# ReceiverShield.net
KiCad netlist of a schematic drawn in EAGLE
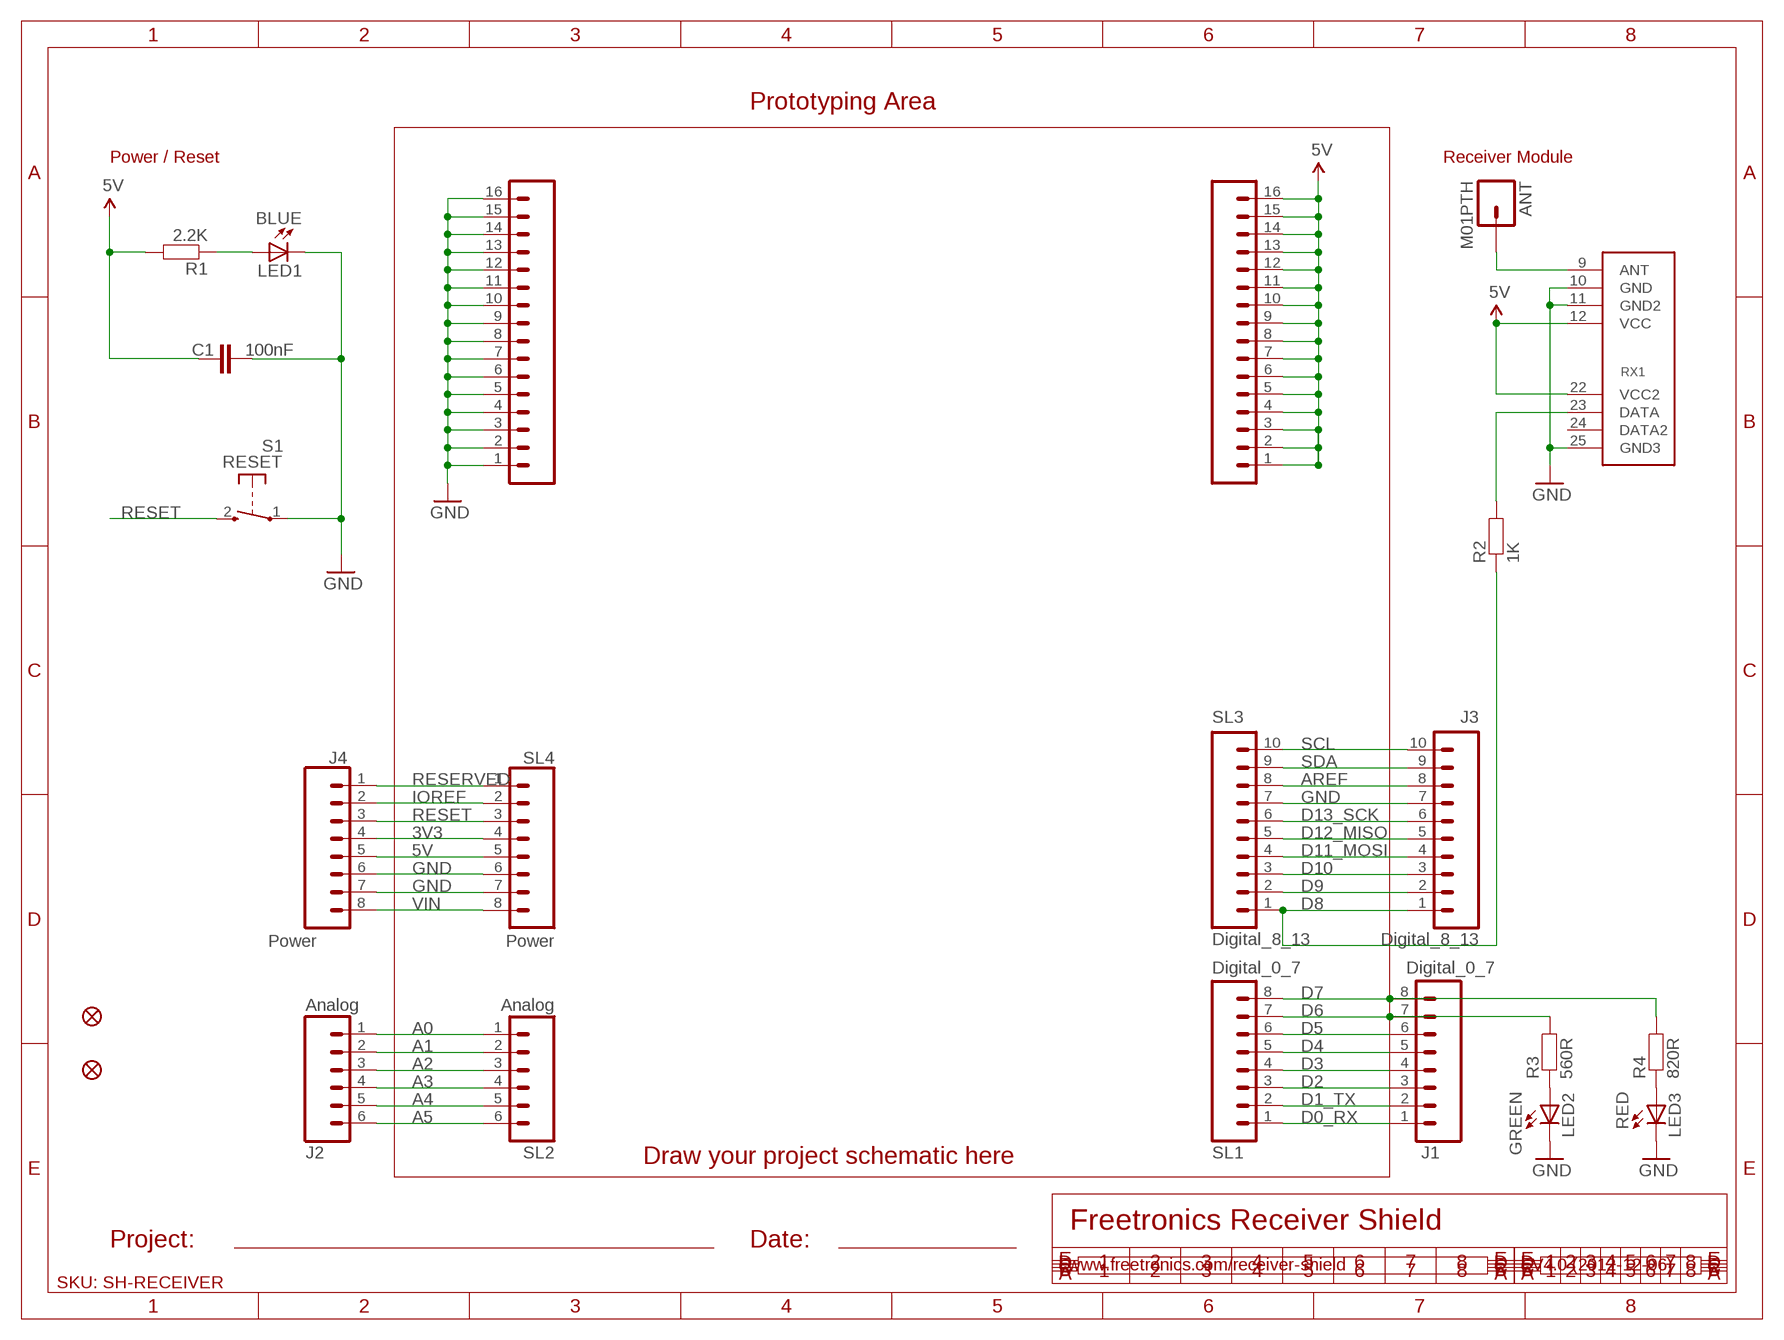
[diagram p0: schematic, sheet 1]

(export (version "E")
  (design (tool "Eeschema 10.0.6"))
  (components
    (comp (ref "ANT")
      (value "M01PTH")
      (footprint "eagle-import:1X01")
      (libsource (lib "eagle-import") (part "M01PTH"))
    )
    (comp (ref "C1")
      (value "100nF")
      (footprint "eagle-import:0603")
      (libsource (lib "eagle-import") (part "CAP0603"))
    )
    (comp (ref "J1")
      (value "Digital_0_7")
      (footprint "eagle-import:1X08")
      (libsource (lib "eagle-import") (part "M08"))
    )
    (comp (ref "J2")
      (value "Analog")
      (footprint "eagle-import:1X06")
      (libsource (lib "eagle-import") (part "M06SIP"))
    )
    (comp (ref "J3")
      (value "Digital_8_13")
      (footprint "eagle-import:1X10")
      (libsource (lib "eagle-import") (part "M100.1"))
    )
    (comp (ref "J4")
      (value "Power")
      (footprint "eagle-import:1X08")
      (libsource (lib "eagle-import") (part "M08"))
    )
    (comp (ref "LED1")
      (value "BLUE")
      (footprint "eagle-import:LED-0603")
      (libsource (lib "eagle-import") (part "LED0603"))
    )
    (comp (ref "LED2")
      (value "GREEN")
      (footprint "eagle-import:LED-0603")
      (libsource (lib "eagle-import") (part "LED0603"))
    )
    (comp (ref "LED3")
      (value "RED")
      (footprint "eagle-import:LED-0603")
      (libsource (lib "eagle-import") (part "LED0603"))
    )
    (comp (ref "PADS_5V")
      (value "M16PTH")
      (footprint "eagle-import:1X16")
      (libsource (lib "eagle-import") (part "M16PTH"))
    )
    (comp (ref "PADS_GND")
      (value "M16PTH")
      (footprint "eagle-import:1X16")
      (libsource (lib "eagle-import") (part "M16PTH"))
    )
    (comp (ref "R1")
      (value "2.2K")
      (footprint "eagle-import:0603")
      (libsource (lib "eagle-import") (part "RESISTOR0603"))
    )
    (comp (ref "R2")
      (value "1K")
      (footprint "eagle-import:0603")
      (libsource (lib "eagle-import") (part "RESISTOR0603"))
    )
    (comp (ref "R3")
      (value "560R")
      (footprint "eagle-import:0603")
      (libsource (lib "eagle-import") (part "RESISTOR0603"))
    )
    (comp (ref "R4")
      (value "820R")
      (footprint "eagle-import:0603")
      (libsource (lib "eagle-import") (part "RESISTOR0603"))
    )
    (comp (ref "RX1")
      (value "RXB1SIL")
      (footprint "eagle-import:RX-B1")
      (libsource (lib "eagle-import") (part "RXB1SIL"))
    )
    (comp (ref "S1")
      (value "RESET")
      (footprint "eagle-import:TACTILE_SWITCH_SMD_2PIN_TINY")
      (libsource (lib "eagle-import") (part "TAC_SWITCH_2PIN"))
    )
    (comp (ref "SL1")
      (value "Digital_0_7")
      (footprint "eagle-import:1X08")
      (libsource (lib "eagle-import") (part "M08"))
    )
    (comp (ref "SL2")
      (value "Analog")
      (footprint "eagle-import:1X06")
      (libsource (lib "eagle-import") (part "M06SIP"))
    )
    (comp (ref "SL3")
      (value "Digital_8_13")
      (footprint "eagle-import:1X10")
      (libsource (lib "eagle-import") (part "M100.1"))
    )
    (comp (ref "SL4")
      (value "Power")
      (footprint "eagle-import:1X08")
      (libsource (lib "eagle-import") (part "M08"))
    )
    (comp (ref "U$4")
      (value "FIDUCIAL1X2.5")
      (footprint "eagle-import:FIDUCIAL-1X2.5")
      (libsource (lib "eagle-import") (part "FIDUCIAL1X2.5"))
    )
    (comp (ref "U$5")
      (value "FIDUCIAL1X2.5")
      (footprint "eagle-import:FIDUCIAL-1X2.5")
      (libsource (lib "eagle-import") (part "FIDUCIAL1X2.5"))
    )
  )
  (nets
    (net (code "1") (name "/3V3") (class "Default")
      (node (ref "J4") (pin "4") (pinfunction "4_4") (pintype "passive"))
      (node (ref "SL4") (pin "4") (pinfunction "4_4") (pintype "passive"))
    )
    (net (code "2") (name "/A0") (class "Default")
      (node (ref "J2") (pin "1") (pinfunction "1_1") (pintype "passive"))
      (node (ref "SL2") (pin "1") (pinfunction "1_1") (pintype "passive"))
    )
    (net (code "3") (name "/A1") (class "Default")
      (node (ref "J2") (pin "2") (pinfunction "2_2") (pintype "passive"))
      (node (ref "SL2") (pin "2") (pinfunction "2_2") (pintype "passive"))
    )
    (net (code "4") (name "/A2") (class "Default")
      (node (ref "J2") (pin "3") (pinfunction "3_3") (pintype "passive"))
      (node (ref "SL2") (pin "3") (pinfunction "3_3") (pintype "passive"))
    )
    (net (code "5") (name "/A3") (class "Default")
      (node (ref "J2") (pin "4") (pinfunction "4_4") (pintype "passive"))
      (node (ref "SL2") (pin "4") (pinfunction "4_4") (pintype "passive"))
    )
    (net (code "6") (name "/A4") (class "Default")
      (node (ref "J2") (pin "5") (pinfunction "5_5") (pintype "passive"))
      (node (ref "SL2") (pin "5") (pinfunction "5_5") (pintype "passive"))
    )
    (net (code "7") (name "/A5") (class "Default")
      (node (ref "J2") (pin "6") (pinfunction "6_6") (pintype "passive"))
      (node (ref "SL2") (pin "6") (pinfunction "6_6") (pintype "passive"))
    )
    (net (code "8") (name "/AREF") (class "Default")
      (node (ref "J3") (pin "8") (pinfunction "8_8") (pintype "passive"))
      (node (ref "SL3") (pin "8") (pinfunction "8_8") (pintype "passive"))
    )
    (net (code "9") (name "/D0_RX") (class "Default")
      (node (ref "J1") (pin "1") (pinfunction "1_1") (pintype "passive"))
      (node (ref "SL1") (pin "1") (pinfunction "1_1") (pintype "passive"))
    )
    (net (code "10") (name "/D1_TX") (class "Default")
      (node (ref "J1") (pin "2") (pinfunction "2_2") (pintype "passive"))
      (node (ref "SL1") (pin "2") (pinfunction "2_2") (pintype "passive"))
    )
    (net (code "11") (name "/D2") (class "Default")
      (node (ref "J1") (pin "3") (pinfunction "3_3") (pintype "passive"))
      (node (ref "SL1") (pin "3") (pinfunction "3_3") (pintype "passive"))
    )
    (net (code "12") (name "/D3") (class "Default")
      (node (ref "J1") (pin "4") (pinfunction "4_4") (pintype "passive"))
      (node (ref "SL1") (pin "4") (pinfunction "4_4") (pintype "passive"))
    )
    (net (code "13") (name "/D4") (class "Default")
      (node (ref "J1") (pin "5") (pinfunction "5_5") (pintype "passive"))
      (node (ref "SL1") (pin "5") (pinfunction "5_5") (pintype "passive"))
    )
    (net (code "14") (name "/D5") (class "Default")
      (node (ref "J1") (pin "6") (pinfunction "6_6") (pintype "passive"))
      (node (ref "SL1") (pin "6") (pinfunction "6_6") (pintype "passive"))
    )
    (net (code "15") (name "/D6") (class "Default")
      (node (ref "J1") (pin "7") (pinfunction "7_7") (pintype "passive"))
      (node (ref "R3") (pin "2") (pinfunction "2_2") (pintype "passive"))
      (node (ref "SL1") (pin "7") (pinfunction "7_7") (pintype "passive"))
    )
    (net (code "16") (name "/D7") (class "Default")
      (node (ref "J1") (pin "8") (pinfunction "8_8") (pintype "passive"))
      (node (ref "R4") (pin "2") (pinfunction "2_2") (pintype "passive"))
      (node (ref "SL1") (pin "8") (pinfunction "8_8") (pintype "passive"))
    )
    (net (code "17") (name "/D8") (class "Default")
      (node (ref "J3") (pin "1") (pinfunction "1_1") (pintype "passive"))
      (node (ref "R2") (pin "1") (pinfunction "1_1") (pintype "passive"))
      (node (ref "SL3") (pin "1") (pinfunction "1_1") (pintype "passive"))
    )
    (net (code "18") (name "/D9") (class "Default")
      (node (ref "J3") (pin "2") (pinfunction "2_2") (pintype "passive"))
      (node (ref "SL3") (pin "2") (pinfunction "2_2") (pintype "passive"))
    )
    (net (code "19") (name "/D10") (class "Default")
      (node (ref "J3") (pin "3") (pinfunction "3_3") (pintype "passive"))
      (node (ref "SL3") (pin "3") (pinfunction "3_3") (pintype "passive"))
    )
    (net (code "20") (name "/D11_MOSI") (class "Default")
      (node (ref "J3") (pin "4") (pinfunction "4_4") (pintype "passive"))
      (node (ref "SL3") (pin "4") (pinfunction "4_4") (pintype "passive"))
    )
    (net (code "21") (name "/D12_MISO") (class "Default")
      (node (ref "J3") (pin "5") (pinfunction "5_5") (pintype "passive"))
      (node (ref "SL3") (pin "5") (pinfunction "5_5") (pintype "passive"))
    )
    (net (code "22") (name "/D13_SCK") (class "Default")
      (node (ref "J3") (pin "6") (pinfunction "6_6") (pintype "passive"))
      (node (ref "SL3") (pin "6") (pinfunction "6_6") (pintype "passive"))
    )
    (net (code "23") (name "/IOREF") (class "Default")
      (node (ref "J4") (pin "2") (pinfunction "2_2") (pintype "passive"))
      (node (ref "SL4") (pin "2") (pinfunction "2_2") (pintype "passive"))
    )
    (net (code "24") (name "/RESERVED") (class "Default")
      (node (ref "J4") (pin "1") (pinfunction "1_1") (pintype "passive"))
      (node (ref "SL4") (pin "1") (pinfunction "1_1") (pintype "passive"))
    )
    (net (code "25") (name "/RESET") (class "Default")
      (node (ref "J4") (pin "3") (pinfunction "3_3") (pintype "passive"))
      (node (ref "S1") (pin "2") (pinfunction "S_2") (pintype "passive"))
      (node (ref "SL4") (pin "3") (pinfunction "3_3") (pintype "passive"))
    )
    (net (code "26") (name "/SCL") (class "Default")
      (node (ref "J3") (pin "10") (pinfunction "10_10") (pintype "passive"))
      (node (ref "SL3") (pin "10") (pinfunction "10_10") (pintype "passive"))
    )
    (net (code "27") (name "/SDA") (class "Default")
      (node (ref "J3") (pin "9") (pinfunction "9_9") (pintype "passive"))
      (node (ref "SL3") (pin "9") (pinfunction "9_9") (pintype "passive"))
    )
    (net (code "28") (name "/VIN") (class "Default")
      (node (ref "J4") (pin "8") (pinfunction "8_8") (pintype "passive"))
      (node (ref "SL4") (pin "8") (pinfunction "8_8") (pintype "passive"))
    )
    (net (code "29") (name "5V") (class "Default")
      (node (ref "C1") (pin "1") (pinfunction "1_1") (pintype "passive"))
      (node (ref "J4") (pin "5") (pinfunction "5_5") (pintype "passive"))
      (node (ref "PADS_5V") (pin "1") (pinfunction "1_1") (pintype "passive"))
      (node (ref "PADS_5V") (pin "10") (pinfunction "10_10") (pintype "passive"))
      (node (ref "PADS_5V") (pin "11") (pinfunction "11_11") (pintype "passive"))
      (node (ref "PADS_5V") (pin "12") (pinfunction "12_12") (pintype "passive"))
      (node (ref "PADS_5V") (pin "13") (pinfunction "13_13") (pintype "passive"))
      (node (ref "PADS_5V") (pin "14") (pinfunction "14_14") (pintype "passive"))
      (node (ref "PADS_5V") (pin "15") (pinfunction "15_15") (pintype "passive"))
      (node (ref "PADS_5V") (pin "16") (pinfunction "16_16") (pintype "passive"))
      (node (ref "PADS_5V") (pin "2") (pinfunction "2_2") (pintype "passive"))
      (node (ref "PADS_5V") (pin "3") (pinfunction "3_3") (pintype "passive"))
      (node (ref "PADS_5V") (pin "4") (pinfunction "4_4") (pintype "passive"))
      (node (ref "PADS_5V") (pin "5") (pinfunction "5_5") (pintype "passive"))
      (node (ref "PADS_5V") (pin "6") (pinfunction "6_6") (pintype "passive"))
      (node (ref "PADS_5V") (pin "7") (pinfunction "7_7") (pintype "passive"))
      (node (ref "PADS_5V") (pin "8") (pinfunction "8_8") (pintype "passive"))
      (node (ref "PADS_5V") (pin "9") (pinfunction "9_9") (pintype "passive"))
      (node (ref "R1") (pin "2") (pinfunction "2_2") (pintype "passive"))
      (node (ref "RX1") (pin "12") (pinfunction "VCC_12") (pintype "bidirectional"))
      (node (ref "RX1") (pin "22") (pinfunction "VCC2_22") (pintype "bidirectional"))
      (node (ref "SL4") (pin "5") (pinfunction "5_5") (pintype "passive"))
    )
    (net (code "30") (name "GND") (class "Default")
      (node (ref "C1") (pin "2") (pinfunction "2_2") (pintype "passive"))
      (node (ref "J3") (pin "7") (pinfunction "7_7") (pintype "passive"))
      (node (ref "J4") (pin "6") (pinfunction "6_6") (pintype "passive"))
      (node (ref "J4") (pin "7") (pinfunction "7_7") (pintype "passive"))
      (node (ref "LED1") (pin "C") (pinfunction "C_C") (pintype "passive"))
      (node (ref "LED2") (pin "C") (pinfunction "C_C") (pintype "passive"))
      (node (ref "LED3") (pin "C") (pinfunction "C_C") (pintype "passive"))
      (node (ref "PADS_GND") (pin "1") (pinfunction "1_1") (pintype "passive"))
      (node (ref "PADS_GND") (pin "10") (pinfunction "10_10") (pintype "passive"))
      (node (ref "PADS_GND") (pin "11") (pinfunction "11_11") (pintype "passive"))
      (node (ref "PADS_GND") (pin "12") (pinfunction "12_12") (pintype "passive"))
      (node (ref "PADS_GND") (pin "13") (pinfunction "13_13") (pintype "passive"))
      (node (ref "PADS_GND") (pin "14") (pinfunction "14_14") (pintype "passive"))
      (node (ref "PADS_GND") (pin "15") (pinfunction "15_15") (pintype "passive"))
      (node (ref "PADS_GND") (pin "16") (pinfunction "16_16") (pintype "passive"))
      (node (ref "PADS_GND") (pin "2") (pinfunction "2_2") (pintype "passive"))
      (node (ref "PADS_GND") (pin "3") (pinfunction "3_3") (pintype "passive"))
      (node (ref "PADS_GND") (pin "4") (pinfunction "4_4") (pintype "passive"))
      (node (ref "PADS_GND") (pin "5") (pinfunction "5_5") (pintype "passive"))
      (node (ref "PADS_GND") (pin "6") (pinfunction "6_6") (pintype "passive"))
      (node (ref "PADS_GND") (pin "7") (pinfunction "7_7") (pintype "passive"))
      (node (ref "PADS_GND") (pin "8") (pinfunction "8_8") (pintype "passive"))
      (node (ref "PADS_GND") (pin "9") (pinfunction "9_9") (pintype "passive"))
      (node (ref "RX1") (pin "10") (pinfunction "GND_10") (pintype "bidirectional"))
      (node (ref "RX1") (pin "11") (pinfunction "GND2_11") (pintype "bidirectional"))
      (node (ref "RX1") (pin "25") (pinfunction "GND3_25") (pintype "bidirectional"))
      (node (ref "S1") (pin "1") (pinfunction "P_1") (pintype "passive"))
      (node (ref "SL3") (pin "7") (pinfunction "7_7") (pintype "passive"))
      (node (ref "SL4") (pin "6") (pinfunction "6_6") (pintype "passive"))
      (node (ref "SL4") (pin "7") (pinfunction "7_7") (pintype "passive"))
    )
    (net (code "31") (name "Net-(LED1-PadA)") (class "Default")
      (node (ref "LED1") (pin "A") (pinfunction "A_A") (pintype "passive"))
      (node (ref "R1") (pin "1") (pinfunction "1_1") (pintype "passive"))
    )
    (net (code "32") (name "Net-(LED2-PadA)") (class "Default")
      (node (ref "LED2") (pin "A") (pinfunction "A_A") (pintype "passive"))
      (node (ref "R3") (pin "1") (pinfunction "1_1") (pintype "passive"))
    )
    (net (code "33") (name "Net-(LED3-PadA)") (class "Default")
      (node (ref "LED3") (pin "A") (pinfunction "A_A") (pintype "passive"))
      (node (ref "R4") (pin "1") (pinfunction "1_1") (pintype "passive"))
    )
    (net (code "34") (name "Net-(RX1-ANT)") (class "Default")
      (node (ref "ANT") (pin "1") (pinfunction "1_1") (pintype "passive"))
      (node (ref "RX1") (pin "9") (pinfunction "ANT_9") (pintype "bidirectional"))
    )
    (net (code "35") (name "Net-(RX1-DATA)") (class "Default")
      (node (ref "R2") (pin "2") (pinfunction "2_2") (pintype "passive"))
      (node (ref "RX1") (pin "23") (pinfunction "DATA_23") (pintype "bidirectional"))
    )
    (net (code "36") (name "unconnected-(RX1-DATA2-Pad24)") (class "Default")
      (node (ref "RX1") (pin "24") (pinfunction "DATA2_24") (pintype "bidirectional"))
    )
  )
)
